# power-adc.net
KiCad netlist of a schematic drawn in Altium Designer
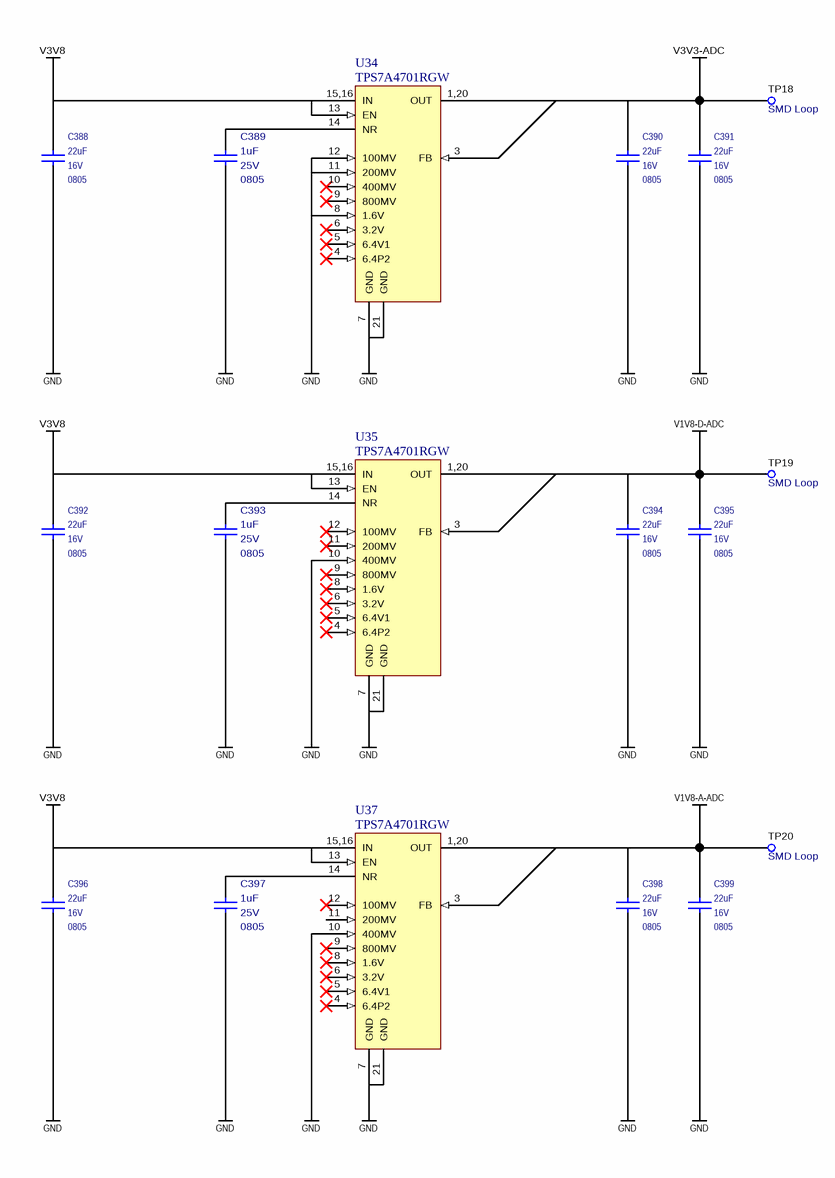
[diagram p0: power-adc.SchDoc]

(export (version "E")
  (design (tool "Eeschema 10.0.6"))
  (components
    (comp (ref "C388")
      (value "22uF")
      (footprint "generic:CAPC200X125X145L45N")
      (description "Ceramic Capacitor 22uF ±20% 16V X5R 0805")
      (fields
        (field (name "MANUFACTURER") "Samsung Electro-Mechanics")
        (field (name "VOLTAGE") "16V")
        (field (name "PACKAGE") "0805")
        (field (name "TOLERANCE") "±20%")
      )
      (libsource (lib "generic") (part "CAP 0603"))
    )
    (comp (ref "C389")
      (value "1uF")
      (footprint "CAPC160X80X90L20N")
      (description "Ceramic Capacitor 1uF ±10% 25V X7R 0805")
      (fields
        (field (name "MANUFACTURER") "Taiyo Yuden")
        (field (name "TOLERANCE") "±10%")
        (field (name "PACKAGE") "0805")
        (field (name "VOLTAGE") "25V")
      )
      (libsource (lib "capacitors") (part "CAP"))
    )
    (comp (ref "C390")
      (value "22uF")
      (footprint "generic:CAPC200X125X145L45N")
      (description "Ceramic Capacitor 22uF ±20% 16V X5R 0805")
      (fields
        (field (name "MANUFACTURER") "Samsung Electro-Mechanics")
        (field (name "VOLTAGE") "16V")
        (field (name "PACKAGE") "0805")
        (field (name "TOLERANCE") "±20%")
      )
      (libsource (lib "generic") (part "CAP 0603"))
    )
    (comp (ref "C391")
      (value "22uF")
      (footprint "generic:CAPC200X125X145L45N")
      (description "Ceramic Capacitor 22uF ±20% 16V X5R 0805")
      (fields
        (field (name "MANUFACTURER") "Samsung Electro-Mechanics")
        (field (name "VOLTAGE") "16V")
        (field (name "PACKAGE") "0805")
        (field (name "TOLERANCE") "±20%")
      )
      (libsource (lib "generic") (part "CAP 0603"))
    )
    (comp (ref "C392")
      (value "22uF")
      (footprint "generic:CAPC200X125X145L45N")
      (description "Ceramic Capacitor 22uF ±20% 16V X5R 0805")
      (fields
        (field (name "MANUFACTURER") "Samsung Electro-Mechanics")
        (field (name "VOLTAGE") "16V")
        (field (name "PACKAGE") "0805")
        (field (name "TOLERANCE") "±20%")
      )
      (libsource (lib "generic") (part "CAP 0603"))
    )
    (comp (ref "C393")
      (value "1uF")
      (footprint "CAPC160X80X90L20N")
      (description "Ceramic Capacitor 1uF ±10% 25V X7R 0805")
      (fields
        (field (name "MANUFACTURER") "Taiyo Yuden")
        (field (name "TOLERANCE") "±10%")
        (field (name "PACKAGE") "0805")
        (field (name "VOLTAGE") "25V")
      )
      (libsource (lib "capacitors") (part "CAP"))
    )
    (comp (ref "C394")
      (value "22uF")
      (footprint "generic:CAPC200X125X145L45N")
      (description "Ceramic Capacitor 22uF ±20% 16V X5R 0805")
      (fields
        (field (name "MANUFACTURER") "Samsung Electro-Mechanics")
        (field (name "VOLTAGE") "16V")
        (field (name "PACKAGE") "0805")
        (field (name "TOLERANCE") "±20%")
      )
      (libsource (lib "generic") (part "CAP 0603"))
    )
    (comp (ref "C395")
      (value "22uF")
      (footprint "generic:CAPC200X125X145L45N")
      (description "Ceramic Capacitor 22uF ±20% 16V X5R 0805")
      (fields
        (field (name "MANUFACTURER") "Samsung Electro-Mechanics")
        (field (name "VOLTAGE") "16V")
        (field (name "PACKAGE") "0805")
        (field (name "TOLERANCE") "±20%")
      )
      (libsource (lib "generic") (part "CAP 0603"))
    )
    (comp (ref "C396")
      (value "22uF")
      (footprint "generic:CAPC200X125X145L45N")
      (description "Ceramic Capacitor 22uF ±20% 16V X5R 0805")
      (fields
        (field (name "MANUFACTURER") "Samsung Electro-Mechanics")
        (field (name "VOLTAGE") "16V")
        (field (name "PACKAGE") "0805")
        (field (name "TOLERANCE") "±20%")
      )
      (libsource (lib "generic") (part "CAP 0603"))
    )
    (comp (ref "C397")
      (value "1uF")
      (footprint "CAPC160X80X90L20N")
      (description "Ceramic Capacitor 1uF ±10% 25V X7R 0805")
      (fields
        (field (name "MANUFACTURER") "Taiyo Yuden")
        (field (name "TOLERANCE") "±10%")
        (field (name "PACKAGE") "0805")
        (field (name "VOLTAGE") "25V")
      )
      (libsource (lib "capacitors") (part "CAP"))
    )
    (comp (ref "C398")
      (value "22uF")
      (footprint "generic:CAPC200X125X145L45N")
      (description "Ceramic Capacitor 22uF ±20% 16V X5R 0805")
      (fields
        (field (name "MANUFACTURER") "Samsung Electro-Mechanics")
        (field (name "VOLTAGE") "16V")
        (field (name "PACKAGE") "0805")
        (field (name "TOLERANCE") "±20%")
      )
      (libsource (lib "generic") (part "CAP 0603"))
    )
    (comp (ref "C399")
      (value "22uF")
      (footprint "generic:CAPC200X125X145L45N")
      (description "Ceramic Capacitor 22uF ±20% 16V X5R 0805")
      (fields
        (field (name "MANUFACTURER") "Samsung Electro-Mechanics")
        (field (name "VOLTAGE") "16V")
        (field (name "PACKAGE") "0805")
        (field (name "TOLERANCE") "±20%")
      )
      (libsource (lib "generic") (part "CAP 0603"))
    )
    (comp (ref "TP18")
      (value "5015")
      (footprint "keystone:5015")
      (description "Test Point SMD")
      (fields (field (name "MANUFACTURER") "Keystone") (field (name "NOTES") "SMD Loop"))
      (libsource (lib "generic") (part "TEST_POINT_SMD_50"))
    )
    (comp (ref "TP19")
      (value "5015")
      (footprint "keystone:5015")
      (description "Test Point SMD")
      (fields (field (name "MANUFACTURER") "Keystone") (field (name "NOTES") "SMD Loop"))
      (libsource (lib "generic") (part "TEST_POINT_SMD_50"))
    )
    (comp (ref "TP20")
      (value "5015")
      (footprint "keystone:5015")
      (description "Test Point SMD")
      (fields (field (name "MANUFACTURER") "Keystone") (field (name "NOTES") "SMD Loop"))
      (libsource (lib "generic") (part "TEST_POINT_SMD_50"))
    )
    (comp (ref "U34")
      (value "TPS7A4701RGW")
      (footprint "QFN65P500X500X100-21N")
      (description "Low-Dropout Linear Regulator 20-VQFN")
      (fields (field (name "MANUFACTURER") "Texas Instruments"))
      (libsource (lib "ti") (part "TPS7A4701RGW_1"))
    )
    (comp (ref "U35")
      (value "TPS7A4701RGW")
      (footprint "QFN65P500X500X100-21N")
      (description "Low-Dropout Linear Regulator 20-VQFN")
      (fields (field (name "MANUFACTURER") "Texas Instruments"))
      (libsource (lib "ti") (part "TPS7A4701RGW_1"))
    )
    (comp (ref "U37")
      (value "TPS7A4701RGW")
      (footprint "QFN65P500X500X100-21N")
      (description "Low-Dropout Linear Regulator 20-VQFN")
      (fields (field (name "MANUFACTURER") "Texas Instruments"))
      (libsource (lib "ti") (part "TPS7A4701RGW_1"))
    )
  )
  (nets
    (net (code "1") (name "GND") (class "Default")
      (node (ref "C388") (pin "1") (pinfunction "1_1") (pintype "passive"))
      (node (ref "C389") (pin "2") (pinfunction "2_2") (pintype "passive"))
      (node (ref "C390") (pin "1") (pinfunction "1_1") (pintype "passive"))
      (node (ref "C391") (pin "1") (pinfunction "1_1") (pintype "passive"))
      (node (ref "C392") (pin "1") (pinfunction "1_1") (pintype "passive"))
      (node (ref "C393") (pin "2") (pinfunction "2_2") (pintype "passive"))
      (node (ref "C394") (pin "1") (pinfunction "1_1") (pintype "passive"))
      (node (ref "C395") (pin "1") (pinfunction "1_1") (pintype "passive"))
      (node (ref "C396") (pin "1") (pinfunction "1_1") (pintype "passive"))
      (node (ref "C397") (pin "2") (pinfunction "2_2") (pintype "passive"))
      (node (ref "C398") (pin "1") (pinfunction "1_1") (pintype "passive"))
      (node (ref "C399") (pin "1") (pinfunction "1_1") (pintype "passive"))
      (node (ref "U34") (pin "11") (pinfunction "200MV_11") (pintype "input"))
      (node (ref "U34") (pin "12") (pinfunction "100MV_12") (pintype "input"))
      (node (ref "U34") (pin "21") (pinfunction "GND_21") (pintype "power_in"))
      (node (ref "U34") (pin "7") (pinfunction "GND_7") (pintype "power_in"))
      (node (ref "U34") (pin "8") (pinfunction "1.6V_8") (pintype "input"))
      (node (ref "U35") (pin "10") (pinfunction "400MV_10") (pintype "input"))
      (node (ref "U35") (pin "21") (pinfunction "GND_21") (pintype "power_in"))
      (node (ref "U35") (pin "7") (pinfunction "GND_7") (pintype "power_in"))
      (node (ref "U37") (pin "10") (pinfunction "400MV_10") (pintype "input"))
      (node (ref "U37") (pin "21") (pinfunction "GND_21") (pintype "power_in"))
      (node (ref "U37") (pin "7") (pinfunction "GND_7") (pintype "power_in"))
    )
    (net (code "2") (name "Net-(U34-NR)") (class "Default")
      (node (ref "C389") (pin "1") (pinfunction "1_1") (pintype "passive"))
      (node (ref "U34") (pin "14") (pinfunction "NR_14") (pintype "passive"))
    )
    (net (code "3") (name "Net-(U35-NR)") (class "Default")
      (node (ref "C393") (pin "1") (pinfunction "1_1") (pintype "passive"))
      (node (ref "U35") (pin "14") (pinfunction "NR_14") (pintype "passive"))
    )
    (net (code "4") (name "Net-(U37-NR)") (class "Default")
      (node (ref "C397") (pin "1") (pinfunction "1_1") (pintype "passive"))
      (node (ref "U37") (pin "14") (pinfunction "NR_14") (pintype "passive"))
    )
    (net (code "5") (name "V1V8-A-ADC") (class "Default")
      (node (ref "C398") (pin "2") (pinfunction "2_2") (pintype "passive"))
      (node (ref "C399") (pin "2") (pinfunction "2_2") (pintype "passive"))
      (node (ref "TP20") (pin "1") (pinfunction "1_1") (pintype "passive"))
      (node (ref "U37") (pin "1") (pinfunction "OUT_1") (pintype "passive"))
      (node (ref "U37") (pin "20") (pinfunction "OUT_20") (pintype "passive"))
      (node (ref "U37") (pin "3") (pinfunction "FB_3") (pintype "input"))
    )
    (net (code "6") (name "V1V8-D-ADC") (class "Default")
      (node (ref "C394") (pin "2") (pinfunction "2_2") (pintype "passive"))
      (node (ref "C395") (pin "2") (pinfunction "2_2") (pintype "passive"))
      (node (ref "TP19") (pin "1") (pinfunction "1_1") (pintype "passive"))
      (node (ref "U35") (pin "1") (pinfunction "OUT_1") (pintype "passive"))
      (node (ref "U35") (pin "20") (pinfunction "OUT_20") (pintype "passive"))
      (node (ref "U35") (pin "3") (pinfunction "FB_3") (pintype "input"))
    )
    (net (code "7") (name "V3V3-ADC") (class "Default")
      (node (ref "C390") (pin "2") (pinfunction "2_2") (pintype "passive"))
      (node (ref "C391") (pin "2") (pinfunction "2_2") (pintype "passive"))
      (node (ref "TP18") (pin "1") (pinfunction "1_1") (pintype "passive"))
      (node (ref "U34") (pin "1") (pinfunction "OUT_1") (pintype "passive"))
      (node (ref "U34") (pin "20") (pinfunction "OUT_20") (pintype "passive"))
      (node (ref "U34") (pin "3") (pinfunction "FB_3") (pintype "input"))
    )
    (net (code "8") (name "V3V8") (class "Default")
      (node (ref "C388") (pin "2") (pinfunction "2_2") (pintype "passive"))
      (node (ref "C392") (pin "2") (pinfunction "2_2") (pintype "passive"))
      (node (ref "C396") (pin "2") (pinfunction "2_2") (pintype "passive"))
      (node (ref "U34") (pin "13") (pinfunction "EN_13") (pintype "input"))
      (node (ref "U34") (pin "15") (pinfunction "IN_15") (pintype "passive"))
      (node (ref "U34") (pin "16") (pinfunction "IN_16") (pintype "passive"))
      (node (ref "U35") (pin "13") (pinfunction "EN_13") (pintype "input"))
      (node (ref "U35") (pin "15") (pinfunction "IN_15") (pintype "passive"))
      (node (ref "U35") (pin "16") (pinfunction "IN_16") (pintype "passive"))
      (node (ref "U37") (pin "13") (pinfunction "EN_13") (pintype "input"))
      (node (ref "U37") (pin "15") (pinfunction "IN_15") (pintype "passive"))
      (node (ref "U37") (pin "16") (pinfunction "IN_16") (pintype "passive"))
    )
    (net (code "9") (name "unconnected-(U34-3.2V-Pad6)") (class "Default")
      (node (ref "U34") (pin "6") (pinfunction "3.2V_6") (pintype "input+no_connect"))
    )
    (net (code "10") (name "unconnected-(U34-6.4P2-Pad4)") (class "Default")
      (node (ref "U34") (pin "4") (pinfunction "6.4P2_4") (pintype "input+no_connect"))
    )
    (net (code "11") (name "unconnected-(U34-6.4V1-Pad5)") (class "Default")
      (node (ref "U34") (pin "5") (pinfunction "6.4V1_5") (pintype "input+no_connect"))
    )
    (net (code "12") (name "unconnected-(U34-400MV-Pad10)") (class "Default")
      (node (ref "U34") (pin "10") (pinfunction "400MV_10") (pintype "input+no_connect"))
    )
    (net (code "13") (name "unconnected-(U34-800MV-Pad9)") (class "Default")
      (node (ref "U34") (pin "9") (pinfunction "800MV_9") (pintype "input+no_connect"))
    )
    (net (code "14") (name "unconnected-(U35-1.6V-Pad8)") (class "Default")
      (node (ref "U35") (pin "8") (pinfunction "1.6V_8") (pintype "input+no_connect"))
    )
    (net (code "15") (name "unconnected-(U35-3.2V-Pad6)") (class "Default")
      (node (ref "U35") (pin "6") (pinfunction "3.2V_6") (pintype "input+no_connect"))
    )
    (net (code "16") (name "unconnected-(U35-6.4P2-Pad4)") (class "Default")
      (node (ref "U35") (pin "4") (pinfunction "6.4P2_4") (pintype "input+no_connect"))
    )
    (net (code "17") (name "unconnected-(U35-6.4V1-Pad5)") (class "Default")
      (node (ref "U35") (pin "5") (pinfunction "6.4V1_5") (pintype "input+no_connect"))
    )
    (net (code "18") (name "unconnected-(U35-100MV-Pad12)") (class "Default")
      (node (ref "U35") (pin "12") (pinfunction "100MV_12") (pintype "input+no_connect"))
    )
    (net (code "19") (name "unconnected-(U35-200MV-Pad11)") (class "Default")
      (node (ref "U35") (pin "11") (pinfunction "200MV_11") (pintype "input+no_connect"))
    )
    (net (code "20") (name "unconnected-(U35-800MV-Pad9)") (class "Default")
      (node (ref "U35") (pin "9") (pinfunction "800MV_9") (pintype "input+no_connect"))
    )
    (net (code "21") (name "unconnected-(U37-1.6V-Pad8)") (class "Default")
      (node (ref "U37") (pin "8") (pinfunction "1.6V_8") (pintype "input+no_connect"))
    )
    (net (code "22") (name "unconnected-(U37-3.2V-Pad6)") (class "Default")
      (node (ref "U37") (pin "6") (pinfunction "3.2V_6") (pintype "input+no_connect"))
    )
    (net (code "23") (name "unconnected-(U37-6.4P2-Pad4)") (class "Default")
      (node (ref "U37") (pin "4") (pinfunction "6.4P2_4") (pintype "input+no_connect"))
    )
    (net (code "24") (name "unconnected-(U37-6.4V1-Pad5)") (class "Default")
      (node (ref "U37") (pin "5") (pinfunction "6.4V1_5") (pintype "input+no_connect"))
    )
    (net (code "25") (name "unconnected-(U37-100MV-Pad12)") (class "Default")
      (node (ref "U37") (pin "12") (pinfunction "100MV_12") (pintype "input+no_connect"))
    )
    (net (code "26") (name "unconnected-(U37-200MV-Pad11)") (class "Default")
      (node (ref "U37") (pin "11") (pinfunction "200MV_11") (pintype "input"))
    )
    (net (code "27") (name "unconnected-(U37-800MV-Pad9)") (class "Default")
      (node (ref "U37") (pin "9") (pinfunction "800MV_9") (pintype "input+no_connect"))
    )
  )
)
